# femtoduinoUSB.net
KiCad netlist of a schematic drawn in EAGLE
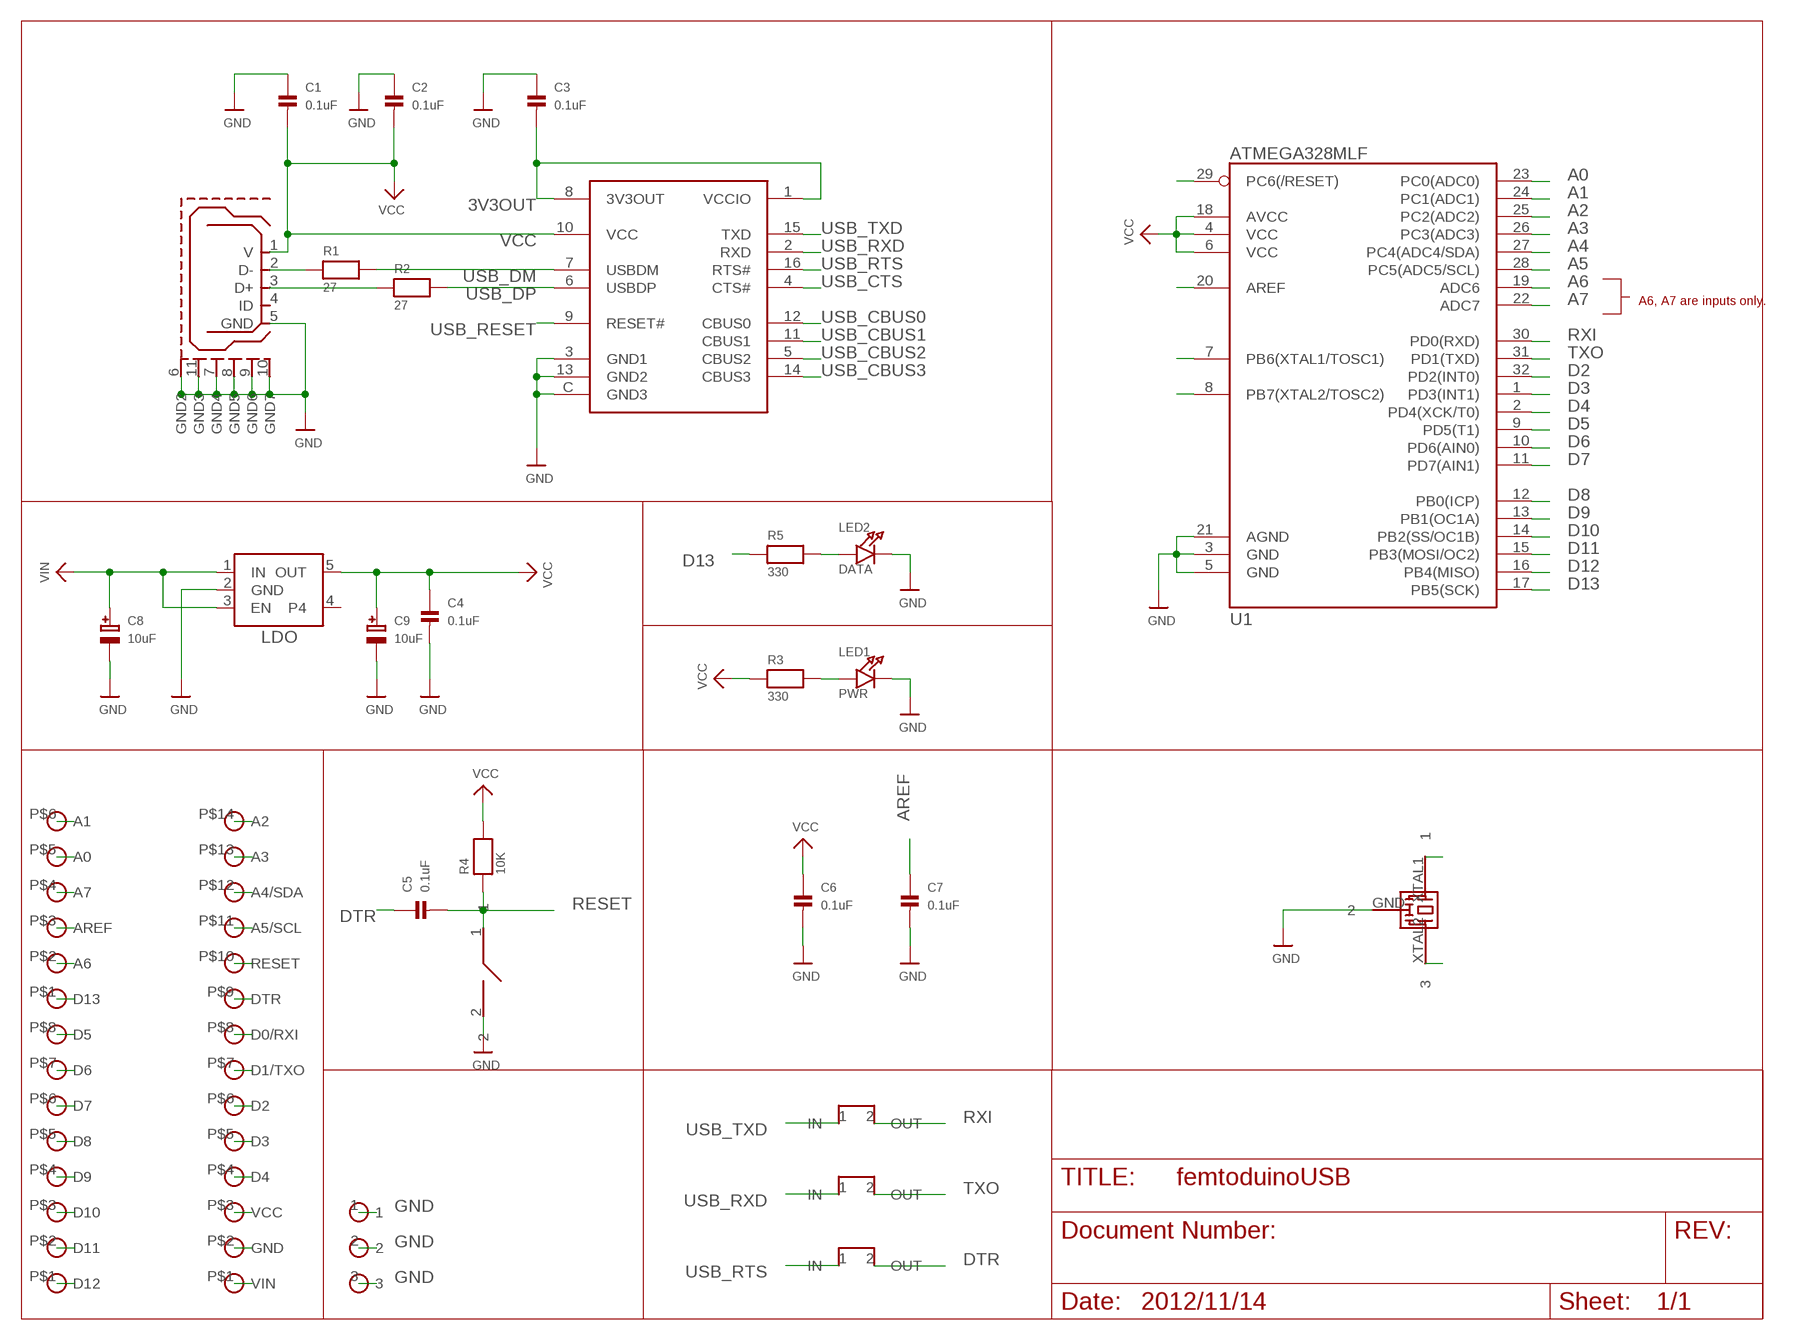
[diagram p0: schematic, sheet 1]

(export (version "E")
  (design (tool "Eeschema 10.0.6"))
  (components
    (comp (ref "C1")
      (value "0.1uF")
      (footprint "eagle-import:_0402")
      (libsource (lib "eagle-import") (part "CAP_CERAMIC_0402"))
    )
    (comp (ref "C2")
      (value "0.1uF")
      (footprint "eagle-import:_0402")
      (libsource (lib "eagle-import") (part "CAP_CERAMIC_0402"))
    )
    (comp (ref "C3")
      (value "0.1uF")
      (footprint "eagle-import:_0402")
      (libsource (lib "eagle-import") (part "CAP_CERAMIC_0402"))
    )
    (comp (ref "C4")
      (value "0.1uF")
      (footprint "eagle-import:_0402MP")
      (libsource (lib "eagle-import") (part "CAP_CERAMIC_0402MP"))
    )
    (comp (ref "C5")
      (value "0.1uF")
      (footprint "eagle-import:_0402MP")
      (libsource (lib "eagle-import") (part "CAP_CERAMIC_0402MP"))
    )
    (comp (ref "C6")
      (value "0.1uF")
      (footprint "eagle-import:_0402MP")
      (libsource (lib "eagle-import") (part "CAP_CERAMIC_0402MP"))
    )
    (comp (ref "C7")
      (value "0.1uF")
      (footprint "eagle-import:_0402")
      (libsource (lib "eagle-import") (part "CAP_CERAMIC_0402"))
    )
    (comp (ref "C8")
      (value "10uF")
      (footprint "eagle-import:EIA3216-18_A-R")
      (libsource (lib "eagle-import") (part "CAP_TANTALUMA/3216_REFLOW"))
    )
    (comp (ref "C9")
      (value "10uF")
      (footprint "eagle-import:EIA3216-18_A-R")
      (libsource (lib "eagle-import") (part "CAP_TANTALUMA/3216_REFLOW"))
    )
    (comp (ref "LED1")
      (value "PWR")
      (footprint "eagle-import:CHIPLED_0603_NOOUTLINE")
      (libsource (lib "eagle-import") (part "LED0603_NOOUTLINE"))
    )
    (comp (ref "LED2")
      (value "DATA")
      (footprint "eagle-import:CHIPLED_0603_NOOUTLINE")
      (libsource (lib "eagle-import") (part "LED0603_NOOUTLINE"))
    )
    (comp (ref "R1")
      (value "27")
      (footprint "eagle-import:_0402")
      (libsource (lib "eagle-import") (part "RESISTOR_0402"))
    )
    (comp (ref "R2")
      (value "27")
      (footprint "eagle-import:_0402")
      (libsource (lib "eagle-import") (part "RESISTOR_0402"))
    )
    (comp (ref "R3")
      (value "330")
      (footprint "eagle-import:_0402MP")
      (libsource (lib "eagle-import") (part "RESISTOR_0402MP"))
    )
    (comp (ref "R4")
      (value "10K")
      (footprint "eagle-import:_0402")
      (libsource (lib "eagle-import") (part "RESISTOR_0402"))
    )
    (comp (ref "R5")
      (value "330")
      (footprint "eagle-import:_0402")
      (libsource (lib "eagle-import") (part "RESISTOR_0402"))
    )
    (comp (ref "U$1")
      (value "FT230XQ")
      (footprint "eagle-import:FT230XQ")
      (libsource (lib "eagle-import") (part "FT230XQ"))
    )
    (comp (ref "U$2")
      (value "05_PINHEAD_1X6")
      (footprint "eagle-import:05_PINHEAD_1X6_PACKAGE")
      (libsource (lib "eagle-import") (part "05_PINHEAD_1X6"))
    )
    (comp (ref "U$3")
      (value "05_PINHEAD_1X8")
      (footprint "eagle-import:05_PINHEAD_1X8_PACKAGE")
      (libsource (lib "eagle-import") (part "05_PINHEAD_1X8"))
    )
    (comp (ref "U$4")
      (value "05_PINHEAD_1X14")
      (footprint "eagle-import:05_PINHEAD_1X14_PACKAGE")
      (libsource (lib "eagle-import") (part "05_PINHEAD_1X14"))
    )
    (comp (ref "U$6")
      (value "USB_MICROB")
      (footprint "eagle-import:USB_MICROB_PACKAGE")
      (libsource (lib "eagle-import") (part "USB_MICROB"))
    )
    (comp (ref "U$10")
      (value "LDO_REGULATOR")
      (footprint "eagle-import:LDO_REGULATOR")
      (libsource (lib "eagle-import") (part "LDO_REGULATOR"))
    )
    (comp (ref "U$17")
      (value "SPST_SMD")
      (footprint "eagle-import:SPST_SMD")
      (libsource (lib "eagle-import") (part "SPST_SMD"))
    )
    (comp (ref "U$22")
      (value "CSTCE16MOV51-RO")
      (footprint "eagle-import:CSTCE16M0V51-RO_PACKAGE")
      (libsource (lib "eagle-import") (part "CSTCE16MOV51-RO"))
    )
    (comp (ref "U$25")
      (value "SPST_SMD_CLOSED")
      (footprint "eagle-import:SPST_SMD_CLOSED")
      (libsource (lib "eagle-import") (part "SPST_SMD_CLOSED"))
    )
    (comp (ref "U$26")
      (value "SPST_SMD_CLOSED")
      (footprint "eagle-import:SPST_SMD_CLOSED")
      (libsource (lib "eagle-import") (part "SPST_SMD_CLOSED"))
    )
    (comp (ref "U$27")
      (value "SPST_SMD_CLOSED")
      (footprint "eagle-import:SPST_SMD_CLOSED")
      (libsource (lib "eagle-import") (part "SPST_SMD_CLOSED"))
    )
    (comp (ref "U$28")
      (value "05_PINHEAD_HEADER_1X3")
      (footprint "eagle-import:05_PINHEAD_1X3_HEAD_PACKAGE")
      (libsource (lib "eagle-import") (part "05_PINHEAD_HEADER_1X3"))
    )
    (comp (ref "U1")
      (value "ATMEGA328MLF")
      (footprint "eagle-import:MLF32")
      (libsource (lib "eagle-import") (part "ATMEGA168MLF"))
    )
  )
  (nets
    (net (code "1") (name "/3V3OUT") (class "Default")
      (node (ref "C3") (pin "2") (pinfunction "P$2_2") (pintype "passive"))
      (node (ref "U$1") (pin "1") (pinfunction "VCCIO_1") (pintype "bidirectional"))
      (node (ref "U$1") (pin "8") (pinfunction "3V3OUT_8") (pintype "bidirectional"))
    )
    (net (code "2") (name "/A0") (class "Default")
      (node (ref "U$2") (pin "P$5") (pinfunction "A0_P$5") (pintype "bidirectional"))
      (node (ref "U1") (pin "23") (pinfunction "PC0(ADC0)_23") (pintype "bidirectional"))
    )
    (net (code "3") (name "/A1") (class "Default")
      (node (ref "U$2") (pin "P$6") (pinfunction "A1_P$6") (pintype "bidirectional"))
      (node (ref "U1") (pin "24") (pinfunction "PC1(ADC1)_24") (pintype "bidirectional"))
    )
    (net (code "4") (name "/A2") (class "Default")
      (node (ref "U$4") (pin "P$14") (pinfunction "A2_P$14") (pintype "bidirectional"))
      (node (ref "U1") (pin "25") (pinfunction "PC2(ADC2)_25") (pintype "bidirectional"))
    )
    (net (code "5") (name "/A3") (class "Default")
      (node (ref "U$4") (pin "P$13") (pinfunction "A3_P$13") (pintype "bidirectional"))
      (node (ref "U1") (pin "26") (pinfunction "PC3(ADC3)_26") (pintype "bidirectional"))
    )
    (net (code "6") (name "/A4") (class "Default")
      (node (ref "U$4") (pin "P$12") (pinfunction "A4/SDA_P$12") (pintype "bidirectional"))
      (node (ref "U1") (pin "27") (pinfunction "PC4(ADC4/SDA)_27") (pintype "bidirectional"))
    )
    (net (code "7") (name "/A5") (class "Default")
      (node (ref "U$4") (pin "P$11") (pinfunction "A5/SCL_P$11") (pintype "bidirectional"))
      (node (ref "U1") (pin "28") (pinfunction "PC5(ADC5/SCL)_28") (pintype "bidirectional"))
    )
    (net (code "8") (name "/A6") (class "Default")
      (node (ref "U$2") (pin "P$2") (pinfunction "A6_P$2") (pintype "bidirectional"))
      (node (ref "U1") (pin "19") (pinfunction "ADC6_19") (pintype "bidirectional"))
    )
    (net (code "9") (name "/A7") (class "Default")
      (node (ref "U$2") (pin "P$4") (pinfunction "A7_P$4") (pintype "bidirectional"))
      (node (ref "U1") (pin "22") (pinfunction "ADC7_22") (pintype "bidirectional"))
    )
    (net (code "10") (name "/AREF") (class "Default")
      (node (ref "C7") (pin "1") (pinfunction "P$1_1") (pintype "passive"))
      (node (ref "U$2") (pin "P$3") (pinfunction "AREF_P$3") (pintype "bidirectional"))
      (node (ref "U1") (pin "20") (pinfunction "AREF_20") (pintype "bidirectional"))
    )
    (net (code "11") (name "/D2") (class "Default")
      (node (ref "U$4") (pin "P$6") (pinfunction "D2_P$6") (pintype "bidirectional"))
      (node (ref "U1") (pin "32") (pinfunction "PD2(INT0)_32") (pintype "bidirectional"))
    )
    (net (code "12") (name "/D3") (class "Default")
      (node (ref "U$4") (pin "P$5") (pinfunction "D3_P$5") (pintype "bidirectional"))
      (node (ref "U1") (pin "1") (pinfunction "PD3(INT1)_1") (pintype "bidirectional"))
    )
    (net (code "13") (name "/D4") (class "Default")
      (node (ref "U$4") (pin "P$4") (pinfunction "D4_P$4") (pintype "bidirectional"))
      (node (ref "U1") (pin "2") (pinfunction "PD4(XCK/T0)_2") (pintype "bidirectional"))
    )
    (net (code "14") (name "/D5") (class "Default")
      (node (ref "U$3") (pin "P$8") (pinfunction "D5_P$8") (pintype "bidirectional"))
      (node (ref "U1") (pin "9") (pinfunction "PD5(T1)_9") (pintype "bidirectional"))
    )
    (net (code "15") (name "/D6") (class "Default")
      (node (ref "U$3") (pin "P$7") (pinfunction "D6_P$7") (pintype "bidirectional"))
      (node (ref "U1") (pin "10") (pinfunction "PD6(AIN0)_10") (pintype "bidirectional"))
    )
    (net (code "16") (name "/D7") (class "Default")
      (node (ref "U$3") (pin "P$6") (pinfunction "D7_P$6") (pintype "bidirectional"))
      (node (ref "U1") (pin "11") (pinfunction "PD7(AIN1)_11") (pintype "bidirectional"))
    )
    (net (code "17") (name "/D8") (class "Default")
      (node (ref "U$3") (pin "P$5") (pinfunction "D8_P$5") (pintype "bidirectional"))
      (node (ref "U1") (pin "12") (pinfunction "PB0(ICP)_12") (pintype "bidirectional"))
    )
    (net (code "18") (name "/D9") (class "Default")
      (node (ref "U$3") (pin "P$4") (pinfunction "D9_P$4") (pintype "bidirectional"))
      (node (ref "U1") (pin "13") (pinfunction "PB1(OC1A)_13") (pintype "bidirectional"))
    )
    (net (code "19") (name "/D10") (class "Default")
      (node (ref "U$3") (pin "P$3") (pinfunction "D10_P$3") (pintype "bidirectional"))
      (node (ref "U1") (pin "14") (pinfunction "PB2(SS/OC1B)_14") (pintype "bidirectional"))
    )
    (net (code "20") (name "/D11") (class "Default")
      (node (ref "U$3") (pin "P$2") (pinfunction "D11_P$2") (pintype "bidirectional"))
      (node (ref "U1") (pin "15") (pinfunction "PB3(MOSI/OC2)_15") (pintype "bidirectional"))
    )
    (net (code "21") (name "/D12") (class "Default")
      (node (ref "U$3") (pin "P$1") (pinfunction "D12_P$1") (pintype "bidirectional"))
      (node (ref "U1") (pin "16") (pinfunction "PB4(MISO)_16") (pintype "bidirectional"))
    )
    (net (code "22") (name "/D13") (class "Default")
      (node (ref "R5") (pin "1") (pinfunction "1_1") (pintype "passive"))
      (node (ref "U$2") (pin "P$1") (pinfunction "D13_P$1") (pintype "bidirectional"))
      (node (ref "U1") (pin "17") (pinfunction "PB5(SCK)_17") (pintype "bidirectional"))
    )
    (net (code "23") (name "/DTR") (class "Default")
      (node (ref "C5") (pin "1") (pinfunction "P$1_1") (pintype "passive"))
      (node (ref "U$27") (pin "2") (pinfunction "OUT_2") (pintype "bidirectional"))
      (node (ref "U$4") (pin "P$9") (pinfunction "DTR_P$9") (pintype "bidirectional"))
    )
    (net (code "24") (name "/RESET") (class "Default")
      (node (ref "C5") (pin "2") (pinfunction "P$2_2") (pintype "passive"))
      (node (ref "R4") (pin "1") (pinfunction "1_1") (pintype "passive"))
      (node (ref "U$17") (pin "1") (pinfunction "1_1") (pintype "bidirectional"))
      (node (ref "U$4") (pin "P$10") (pinfunction "RESET_P$10") (pintype "bidirectional"))
      (node (ref "U1") (pin "29") (pinfunction "PC6(/RESET)_29") (pintype "bidirectional"))
    )
    (net (code "25") (name "/RXI") (class "Default")
      (node (ref "U$25") (pin "2") (pinfunction "OUT_2") (pintype "bidirectional"))
      (node (ref "U$4") (pin "P$8") (pinfunction "D0/RXI_P$8") (pintype "bidirectional"))
      (node (ref "U1") (pin "30") (pinfunction "PD0(RXD)_30") (pintype "bidirectional"))
    )
    (net (code "26") (name "/TXO") (class "Default")
      (node (ref "U$26") (pin "2") (pinfunction "OUT_2") (pintype "bidirectional"))
      (node (ref "U$4") (pin "P$7") (pinfunction "D1/TXO_P$7") (pintype "bidirectional"))
      (node (ref "U1") (pin "31") (pinfunction "PD1(TXD)_31") (pintype "bidirectional"))
    )
    (net (code "27") (name "/USB_CBUS0") (class "Default")
      (node (ref "U$1") (pin "12") (pinfunction "CBUS0_12") (pintype "bidirectional"))
    )
    (net (code "28") (name "/USB_CBUS1") (class "Default")
      (node (ref "U$1") (pin "11") (pinfunction "CBUS1_11") (pintype "bidirectional"))
    )
    (net (code "29") (name "/USB_CBUS2") (class "Default")
      (node (ref "U$1") (pin "5") (pinfunction "CBUS2_5") (pintype "bidirectional"))
    )
    (net (code "30") (name "/USB_CBUS3") (class "Default")
      (node (ref "U$1") (pin "14") (pinfunction "CBUS3_14") (pintype "bidirectional"))
    )
    (net (code "31") (name "/USB_CTS") (class "Default")
      (node (ref "U$1") (pin "4") (pinfunction "CTS#_4") (pintype "bidirectional"))
    )
    (net (code "32") (name "/USB_DM") (class "Default")
      (node (ref "R1") (pin "2") (pinfunction "2_2") (pintype "passive"))
      (node (ref "U$1") (pin "7") (pinfunction "USBDM_7") (pintype "bidirectional"))
    )
    (net (code "33") (name "/USB_DP") (class "Default")
      (node (ref "R2") (pin "2") (pinfunction "2_2") (pintype "passive"))
      (node (ref "U$1") (pin "6") (pinfunction "USBDP_6") (pintype "bidirectional"))
    )
    (net (code "34") (name "/USB_RESET") (class "Default")
      (node (ref "U$1") (pin "9") (pinfunction "RESET#_9") (pintype "bidirectional"))
    )
    (net (code "35") (name "/USB_RTS") (class "Default")
      (node (ref "U$1") (pin "16") (pinfunction "RTS#_16") (pintype "bidirectional"))
      (node (ref "U$27") (pin "1") (pinfunction "IN_1") (pintype "bidirectional"))
    )
    (net (code "36") (name "/USB_RXD") (class "Default")
      (node (ref "U$1") (pin "2") (pinfunction "RXD_2") (pintype "bidirectional"))
      (node (ref "U$26") (pin "1") (pinfunction "IN_1") (pintype "bidirectional"))
    )
    (net (code "37") (name "/USB_TXD") (class "Default")
      (node (ref "U$1") (pin "15") (pinfunction "TXD_15") (pintype "bidirectional"))
      (node (ref "U$25") (pin "1") (pinfunction "IN_1") (pintype "bidirectional"))
    )
    (net (code "38") (name "/XTAL1") (class "Default")
      (node (ref "U$22") (pin "XTAL1") (pinfunction "1_XTAL1") (pintype "bidirectional"))
      (node (ref "U1") (pin "7") (pinfunction "PB6(XTAL1/TOSC1)_7") (pintype "bidirectional"))
    )
    (net (code "39") (name "/XTAL2") (class "Default")
      (node (ref "U$22") (pin "XTAL2") (pinfunction "3_XTAL2") (pintype "bidirectional"))
      (node (ref "U1") (pin "8") (pinfunction "PB7(XTAL2/TOSC2)_8") (pintype "bidirectional"))
    )
    (net (code "40") (name "GND") (class "Default")
      (node (ref "C1") (pin "1") (pinfunction "P$1_1") (pintype "passive"))
      (node (ref "C2") (pin "1") (pinfunction "P$1_1") (pintype "passive"))
      (node (ref "C3") (pin "1") (pinfunction "P$1_1") (pintype "passive"))
      (node (ref "C4") (pin "2") (pinfunction "P$2_2") (pintype "passive"))
      (node (ref "C6") (pin "2") (pinfunction "P$2_2") (pintype "passive"))
      (node (ref "C7") (pin "2") (pinfunction "P$2_2") (pintype "passive"))
      (node (ref "C8") (pin "-") (pinfunction "-_-") (pintype "passive"))
      (node (ref "C9") (pin "-") (pinfunction "-_-") (pintype "passive"))
      (node (ref "LED1") (pin "C") (pinfunction "C_C") (pintype "passive"))
      (node (ref "LED2") (pin "C") (pinfunction "C_C") (pintype "passive"))
      (node (ref "U$1") (pin "13") (pinfunction "GND2_13") (pintype "bidirectional"))
      (node (ref "U$1") (pin "3") (pinfunction "GND1_3") (pintype "bidirectional"))
      (node (ref "U$1") (pin "C") (pinfunction "GND3_C") (pintype "bidirectional"))
      (node (ref "U$10") (pin "2") (pinfunction "GND_2") (pintype "bidirectional"))
      (node (ref "U$17") (pin "2") (pinfunction "2_2") (pintype "bidirectional"))
      (node (ref "U$22") (pin "GND") (pinfunction "2_GND") (pintype "bidirectional"))
      (node (ref "U$28") (pin "1") (pinfunction "1_1") (pintype "bidirectional"))
      (node (ref "U$28") (pin "2") (pinfunction "2_2") (pintype "bidirectional"))
      (node (ref "U$28") (pin "3") (pinfunction "3_3") (pintype "bidirectional"))
      (node (ref "U$4") (pin "P$2") (pinfunction "GND_P$2") (pintype "bidirectional"))
      (node (ref "U$6") (pin "10") (pinfunction "GND7_10") (pintype "bidirectional"))
      (node (ref "U$6") (pin "11") (pinfunction "GND3_11") (pintype "bidirectional"))
      (node (ref "U$6") (pin "5") (pinfunction "GND_5") (pintype "bidirectional"))
      (node (ref "U$6") (pin "6") (pinfunction "GND2_6") (pintype "bidirectional"))
      (node (ref "U$6") (pin "7") (pinfunction "GND4_7") (pintype "bidirectional"))
      (node (ref "U$6") (pin "8") (pinfunction "GND5_8") (pintype "bidirectional"))
      (node (ref "U$6") (pin "9") (pinfunction "GND6_9") (pintype "bidirectional"))
      (node (ref "U1") (pin "21") (pinfunction "AGND_21") (pintype "bidirectional"))
      (node (ref "U1") (pin "3") (pinfunction "GND_3") (pintype "bidirectional"))
      (node (ref "U1") (pin "5") (pinfunction "GND_5") (pintype "bidirectional"))
    )
    (net (code "41") (name "Net-(LED1-PadA)") (class "Default")
      (node (ref "LED1") (pin "A") (pinfunction "A_A") (pintype "passive"))
      (node (ref "R3") (pin "2") (pinfunction "2_2") (pintype "passive"))
    )
    (net (code "42") (name "Net-(LED2-PadA)") (class "Default")
      (node (ref "LED2") (pin "A") (pinfunction "A_A") (pintype "passive"))
      (node (ref "R5") (pin "2") (pinfunction "2_2") (pintype "passive"))
    )
    (net (code "43") (name "Net-(U$6-D+)") (class "Default")
      (node (ref "R2") (pin "1") (pinfunction "1_1") (pintype "passive"))
      (node (ref "U$6") (pin "3") (pinfunction "D+_3") (pintype "bidirectional"))
    )
    (net (code "44") (name "Net-(U$6-D-)") (class "Default")
      (node (ref "R1") (pin "1") (pinfunction "1_1") (pintype "passive"))
      (node (ref "U$6") (pin "2") (pinfunction "D-_2") (pintype "bidirectional"))
    )
    (net (code "45") (name "VCC") (class "Default")
      (node (ref "C1") (pin "2") (pinfunction "P$2_2") (pintype "passive"))
      (node (ref "C2") (pin "2") (pinfunction "P$2_2") (pintype "passive"))
      (node (ref "C4") (pin "1") (pinfunction "P$1_1") (pintype "passive"))
      (node (ref "C6") (pin "1") (pinfunction "P$1_1") (pintype "passive"))
      (node (ref "C9") (pin "+") (pinfunction "+_+") (pintype "passive"))
      (node (ref "R3") (pin "1") (pinfunction "1_1") (pintype "passive"))
      (node (ref "R4") (pin "2") (pinfunction "2_2") (pintype "passive"))
      (node (ref "U$1") (pin "10") (pinfunction "VCC_10") (pintype "bidirectional"))
      (node (ref "U$10") (pin "5") (pinfunction "OUT_5") (pintype "bidirectional"))
      (node (ref "U$4") (pin "P$3") (pinfunction "VCC_P$3") (pintype "bidirectional"))
      (node (ref "U$6") (pin "1") (pinfunction "V_1") (pintype "bidirectional"))
      (node (ref "U1") (pin "18") (pinfunction "AVCC_18") (pintype "bidirectional"))
      (node (ref "U1") (pin "4") (pinfunction "VCC_4") (pintype "bidirectional"))
      (node (ref "U1") (pin "6") (pinfunction "VCC_6") (pintype "bidirectional"))
    )
    (net (code "46") (name "VIN") (class "Default")
      (node (ref "C8") (pin "+") (pinfunction "+_+") (pintype "passive"))
      (node (ref "U$10") (pin "1") (pinfunction "IN_1") (pintype "bidirectional"))
      (node (ref "U$10") (pin "3") (pinfunction "EN_3") (pintype "bidirectional"))
      (node (ref "U$4") (pin "P$1") (pinfunction "VIN_P$1") (pintype "bidirectional"))
    )
    (net (code "47") (name "unconnected-(U$6-ID-Pad4)") (class "Default")
      (node (ref "U$6") (pin "4") (pinfunction "ID_4") (pintype "bidirectional"))
    )
    (net (code "48") (name "unconnected-(U$10-P4-Pad4)") (class "Default")
      (node (ref "U$10") (pin "4") (pinfunction "P4_4") (pintype "bidirectional"))
    )
  )
)
